# SHiB64_Mk_1Mod_2.net
KiCad netlist of a schematic drawn in EAGLE
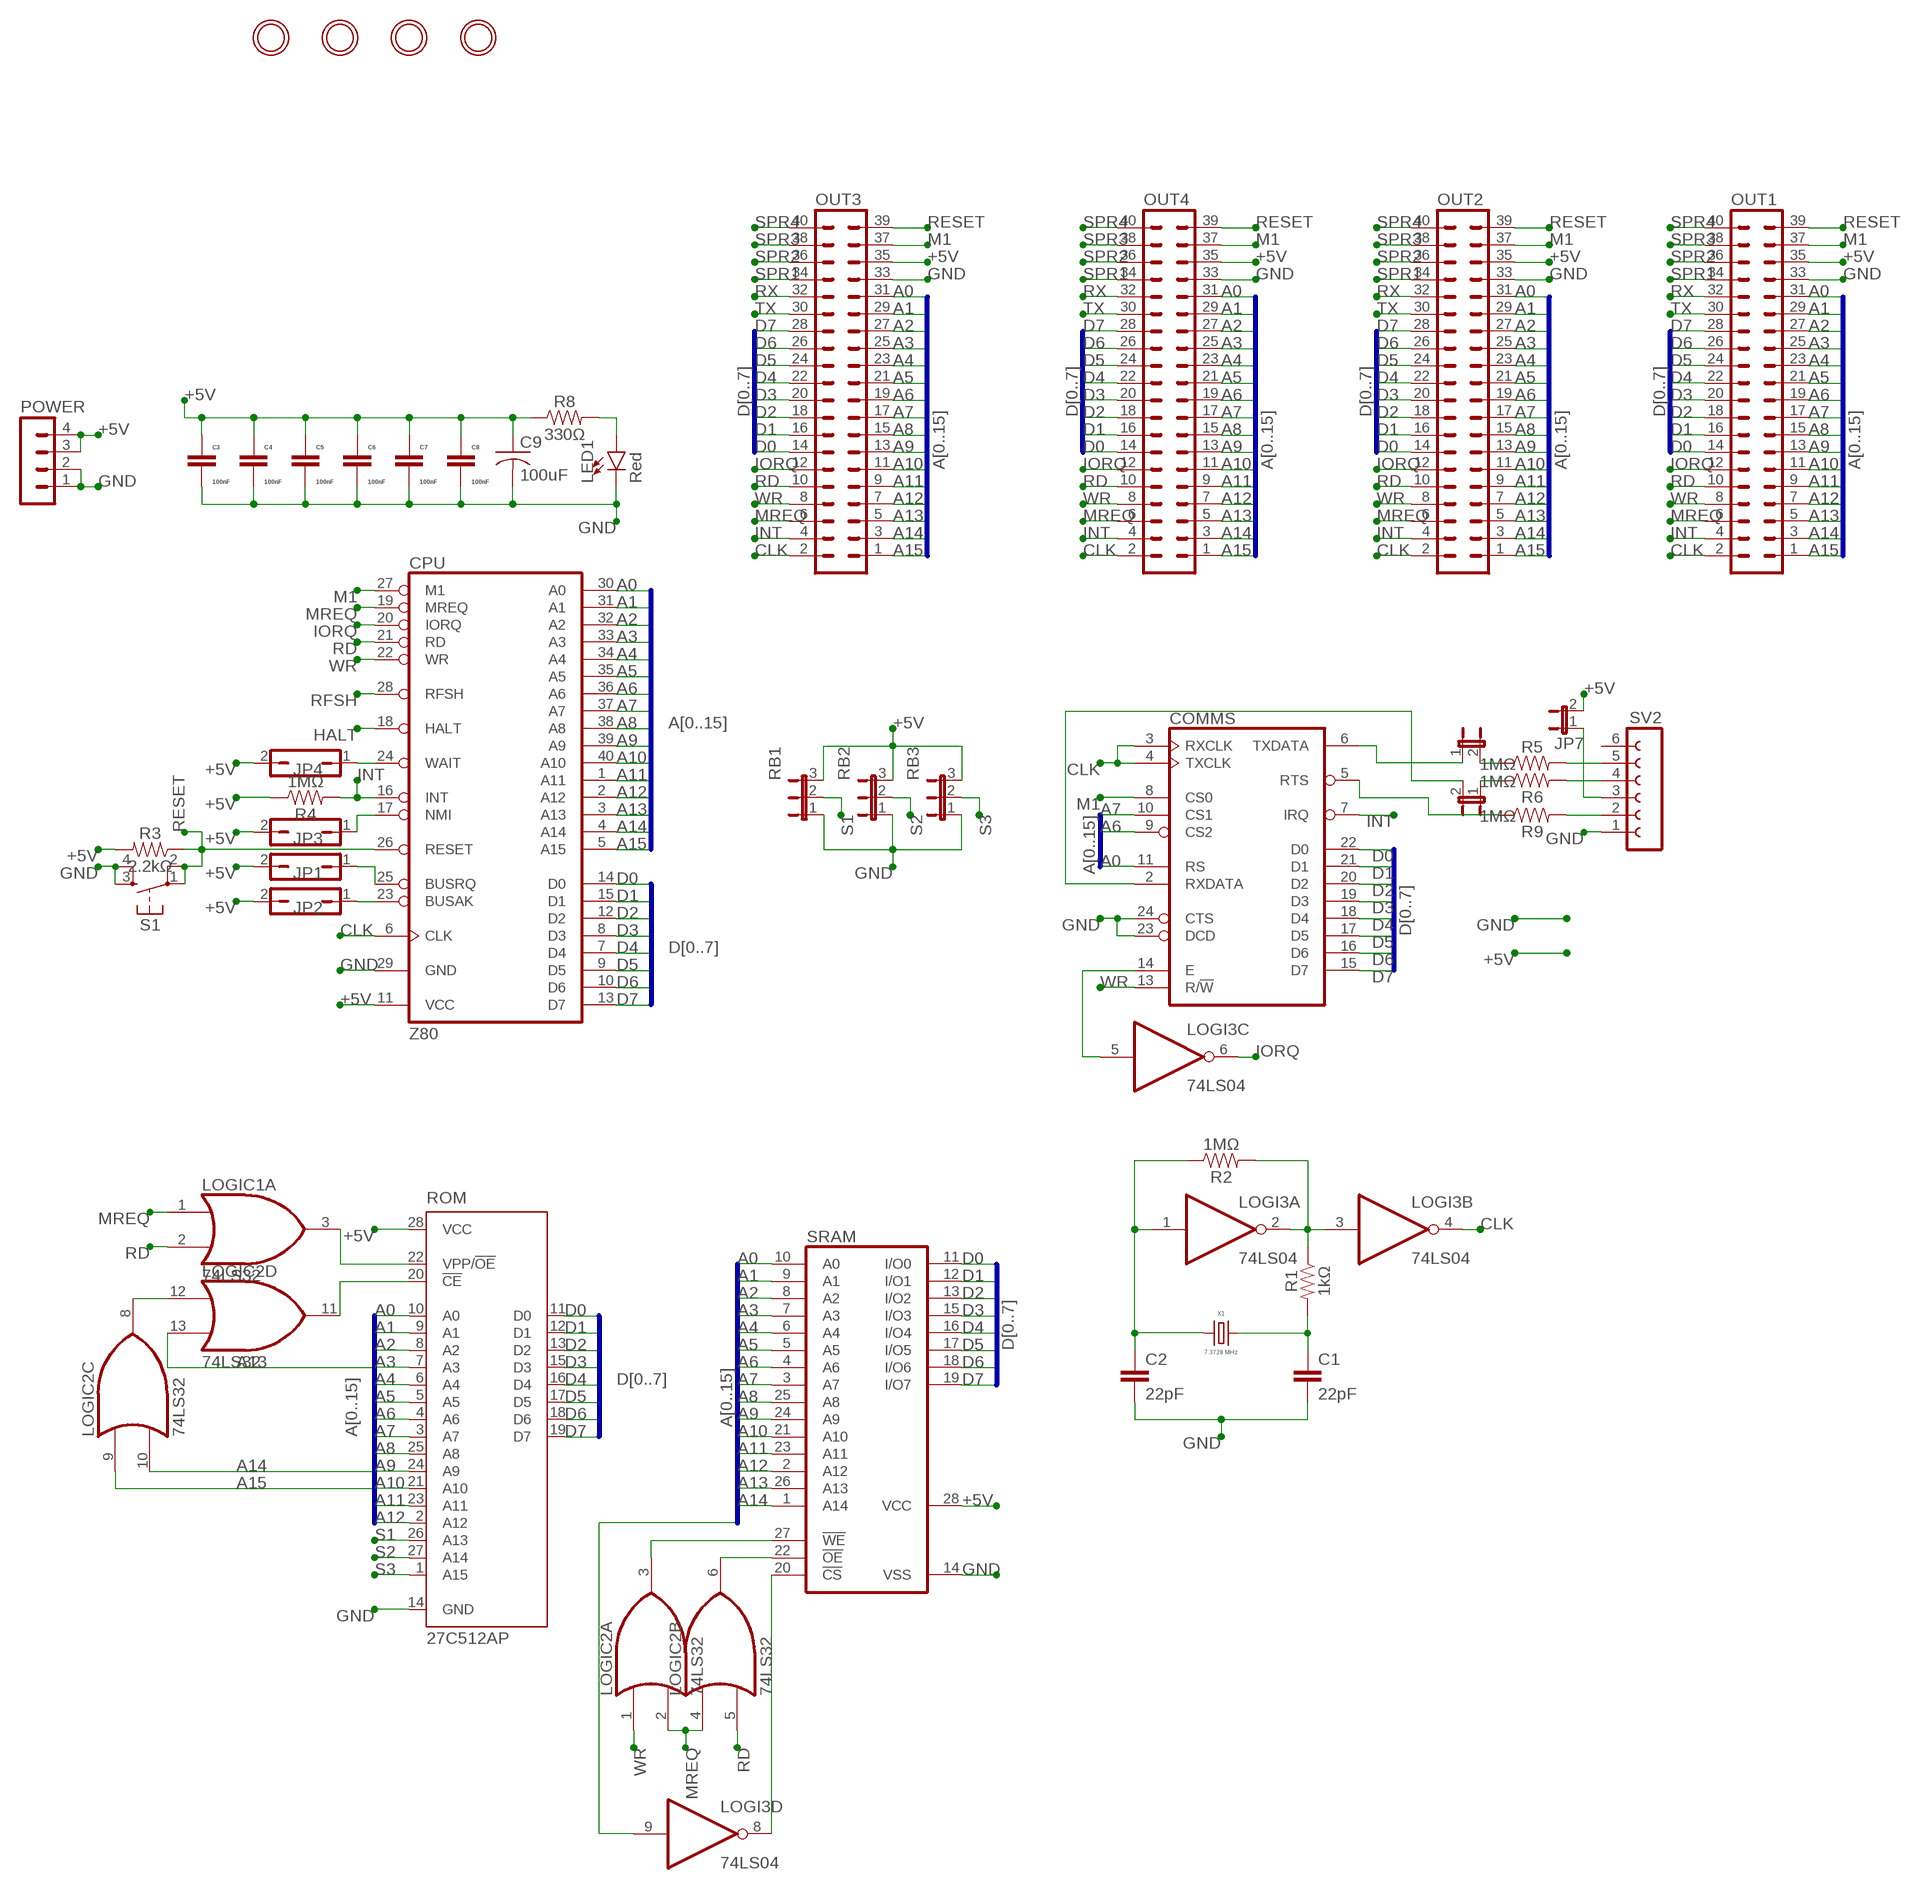
[diagram p0: schematic, sheet 1]

(export (version "E")
  (design (tool "Eeschema 10.0.6"))
  (components
    (comp (ref "C1")
      (value "22pF")
      (footprint "eagle-import:CAP-PTH-2.54")
      (libsource (lib "eagle-import") (part "CAP_DISK"))
    )
    (comp (ref "C2")
      (value "22pF")
      (footprint "eagle-import:CAP-PTH-2.54")
      (libsource (lib "eagle-import") (part "CAP_DISK"))
    )
    (comp (ref "C3")
      (value "100nF")
      (footprint "eagle-import:C1206")
      (libsource (lib "eagle-import") (part "CAPACITOR_1206_NONPPOLAR"))
    )
    (comp (ref "C4")
      (value "100nF")
      (footprint "eagle-import:C1206")
      (libsource (lib "eagle-import") (part "CAPACITOR_1206_NONPPOLAR"))
    )
    (comp (ref "C5")
      (value "100nF")
      (footprint "eagle-import:C1206")
      (libsource (lib "eagle-import") (part "CAPACITOR_1206_NONPPOLAR"))
    )
    (comp (ref "C6")
      (value "100nF")
      (footprint "eagle-import:C1206")
      (libsource (lib "eagle-import") (part "CAPACITOR_1206_NONPPOLAR"))
    )
    (comp (ref "C7")
      (value "100nF")
      (footprint "eagle-import:C1206")
      (libsource (lib "eagle-import") (part "CAPACITOR_1206_NONPPOLAR"))
    )
    (comp (ref "C8")
      (value "100nF")
      (footprint "eagle-import:C1206")
      (libsource (lib "eagle-import") (part "CAPACITOR_1206_NONPPOLAR"))
    )
    (comp (ref "C9")
      (value "100uF")
      (footprint "eagle-import:C1206")
      (libsource (lib "eagle-import") (part "CAPACITOR_1206_POLAR"))
    )
    (comp (ref "COMMS")
      (value "6850")
      (footprint "eagle-import:DIL24")
      (fields (field (name "MF") "NTE ELECTRONICS") (field (name "MPN") "NTE6850"))
      (libsource (lib "eagle-import") (part "6850"))
    )
    (comp (ref "CPU")
      (value "Z80")
      (footprint "eagle-import:DIL40")
      (libsource (lib "eagle-import") (part "Z80CPU"))
    )
    (comp (ref "JP1")
      (value "JP1Q")
      (footprint "eagle-import:JP1")
      (libsource (lib "eagle-import") (part "JP1Q"))
    )
    (comp (ref "JP2")
      (value "JP1Q")
      (footprint "eagle-import:JP1")
      (libsource (lib "eagle-import") (part "JP1Q"))
    )
    (comp (ref "JP3")
      (value "JP1Q")
      (footprint "eagle-import:JP1")
      (libsource (lib "eagle-import") (part "JP1Q"))
    )
    (comp (ref "JP4")
      (value "JP1Q")
      (footprint "eagle-import:JP1")
      (libsource (lib "eagle-import") (part "JP1Q"))
    )
    (comp (ref "JP5")
      (value "JP1E")
      (footprint "eagle-import:JP1")
      (libsource (lib "eagle-import") (part "JP1E"))
    )
    (comp (ref "JP6")
      (value "JP1E")
      (footprint "eagle-import:JP1")
      (libsource (lib "eagle-import") (part "JP1E"))
    )
    (comp (ref "JP7")
      (value "JP1E")
      (footprint "eagle-import:JP1")
      (libsource (lib "eagle-import") (part "JP1E"))
    )
    (comp (ref "LED1")
      (value "Red")
      (footprint "eagle-import:LED_1206")
      (libsource (lib "eagle-import") (part "LED_1206"))
    )
    (comp (ref "LOGI3")
      (value "74LS04")
      (footprint "eagle-import:SO14")
      (libsource (lib "eagle-import") (part "7404DALS"))
    )
    (comp (ref "LOGIC1")
      (value "74LS32")
      (footprint "eagle-import:SO14")
      (libsource (lib "eagle-import") (part "7432DLS"))
    )
    (comp (ref "LOGIC2")
      (value "74LS32")
      (footprint "eagle-import:SO14")
      (libsource (lib "eagle-import") (part "7432DLS"))
    )
    (comp (ref "OUT1")
      (value "MA20-2")
      (footprint "eagle-import:MA20-2")
      (libsource (lib "eagle-import") (part "MA20-2"))
    )
    (comp (ref "OUT2")
      (value "MA20-2")
      (footprint "eagle-import:MA20-2")
      (libsource (lib "eagle-import") (part "MA20-2"))
    )
    (comp (ref "OUT3")
      (value "MA20-2")
      (footprint "eagle-import:MA20-2")
      (libsource (lib "eagle-import") (part "MA20-2"))
    )
    (comp (ref "OUT4")
      (value "MA20-2")
      (footprint "eagle-import:MA20-2")
      (libsource (lib "eagle-import") (part "MA20-2"))
    )
    (comp (ref "POWER")
      (value "MA04-1")
      (footprint "eagle-import:MA04-1")
      (libsource (lib "eagle-import") (part "MA04-1"))
    )
    (comp (ref "R1")
      (value "1kΩ")
      (footprint "eagle-import:R1206")
      (libsource (lib "eagle-import") (part "RESISTOR"))
    )
    (comp (ref "R2")
      (value "1MΩ")
      (footprint "eagle-import:R1206")
      (libsource (lib "eagle-import") (part "RESISTOR"))
    )
    (comp (ref "R3")
      (value "2.2kΩ")
      (footprint "eagle-import:R1206")
      (libsource (lib "eagle-import") (part "RESISTOR"))
    )
    (comp (ref "R4")
      (value "1MΩ")
      (footprint "eagle-import:R1206")
      (libsource (lib "eagle-import") (part "RESISTOR"))
    )
    (comp (ref "R5")
      (value "1MΩ")
      (footprint "eagle-import:R1206")
      (libsource (lib "eagle-import") (part "RESISTOR"))
    )
    (comp (ref "R6")
      (value "1MΩ")
      (footprint "eagle-import:R1206")
      (libsource (lib "eagle-import") (part "RESISTOR"))
    )
    (comp (ref "R8")
      (value "330Ω")
      (footprint "eagle-import:R1206")
      (libsource (lib "eagle-import") (part "RESISTOR"))
    )
    (comp (ref "R9")
      (value "1MΩ")
      (footprint "eagle-import:R1206")
      (libsource (lib "eagle-import") (part "RESISTOR"))
    )
    (comp (ref "RB1")
      (value "JP2E")
      (footprint "eagle-import:JP2")
      (libsource (lib "eagle-import") (part "JP2E"))
    )
    (comp (ref "RB2")
      (value "JP2E")
      (footprint "eagle-import:JP2")
      (libsource (lib "eagle-import") (part "JP2E"))
    )
    (comp (ref "RB3")
      (value "JP2E")
      (footprint "eagle-import:JP2")
      (libsource (lib "eagle-import") (part "JP2E"))
    )
    (comp (ref "ROM")
      (value "27C512AP")
      (footprint "eagle-import:DIL28-6")
      (fields (field (name "MPN") "M27C512-90B6"))
      (libsource (lib "eagle-import") (part "27512APC"))
    )
    (comp (ref "S1")
      (value "MOMENTARY_BUTTONS6MMSMALL")
      (footprint "eagle-import:TACTILE_SWITCH_PTH_6.0MM")
      (libsource (lib "eagle-import") (part "MOMENTARY_BUTTONS6MMSMALL"))
    )
    (comp (ref "SRAM")
      (value "62256P")
      (footprint "eagle-import:DIL28-6")
      (libsource (lib "eagle-import") (part "62256P"))
    )
    (comp (ref "SV2")
      (value "FE06-1")
      (footprint "eagle-import:FE06")
      (libsource (lib "eagle-import") (part "FE06-1"))
    )
    (comp (ref "U$1")
      (value "MOUNTING_HOLE")
      (footprint "eagle-import:MOUNTINGHOLE_3.2MM_PLATEDTHIN")
      (libsource (lib "eagle-import") (part "MOUNTING_HOLE"))
    )
    (comp (ref "U$2")
      (value "MOUNTING_HOLE")
      (footprint "eagle-import:MOUNTINGHOLE_3.2MM_PLATEDTHIN")
      (libsource (lib "eagle-import") (part "MOUNTING_HOLE"))
    )
    (comp (ref "U$3")
      (value "MOUNTING_HOLE")
      (footprint "eagle-import:MOUNTINGHOLE_3.2MM_PLATEDTHIN")
      (libsource (lib "eagle-import") (part "MOUNTING_HOLE"))
    )
    (comp (ref "U$4")
      (value "MOUNTING_HOLE")
      (footprint "eagle-import:MOUNTINGHOLE_3.2MM_PLATEDTHIN")
      (libsource (lib "eagle-import") (part "MOUNTING_HOLE"))
    )
    (comp (ref "X1")
      (value "7.3728 MHz")
      (footprint "eagle-import:HC49US")
      (libsource (lib "eagle-import") (part "CRYSTAL_16MHZ"))
    )
  )
  (nets
    (net (code "1") (name "/+5V") (class "Default")
      (node (ref "C3") (pin "1") (pinfunction "1_1") (pintype "passive"))
      (node (ref "C4") (pin "1") (pinfunction "1_1") (pintype "passive"))
      (node (ref "C5") (pin "1") (pinfunction "1_1") (pintype "passive"))
      (node (ref "C6") (pin "1") (pinfunction "1_1") (pintype "passive"))
      (node (ref "C7") (pin "1") (pinfunction "1_1") (pintype "passive"))
      (node (ref "C8") (pin "1") (pinfunction "1_1") (pintype "passive"))
      (node (ref "C9") (pin "1") (pinfunction "1_1") (pintype "passive"))
      (node (ref "CPU") (pin "11") (pinfunction "VCC_11") (pintype "power_in"))
      (node (ref "JP1") (pin "2") (pinfunction "2_2") (pintype "passive"))
      (node (ref "JP2") (pin "2") (pinfunction "2_2") (pintype "passive"))
      (node (ref "JP3") (pin "2") (pinfunction "2_2") (pintype "passive"))
      (node (ref "JP4") (pin "2") (pinfunction "2_2") (pintype "passive"))
      (node (ref "JP7") (pin "2") (pinfunction "2_2") (pintype "passive"))
      (node (ref "OUT1") (pin "35") (pinfunction "35_35") (pintype "passive"))
      (node (ref "OUT2") (pin "35") (pinfunction "35_35") (pintype "passive"))
      (node (ref "OUT3") (pin "35") (pinfunction "35_35") (pintype "passive"))
      (node (ref "OUT4") (pin "35") (pinfunction "35_35") (pintype "passive"))
      (node (ref "POWER") (pin "3") (pinfunction "3_3") (pintype "passive"))
      (node (ref "POWER") (pin "4") (pinfunction "4_4") (pintype "passive"))
      (node (ref "R3") (pin "2") (pinfunction "2_2") (pintype "passive"))
      (node (ref "R4") (pin "1") (pinfunction "1_1") (pintype "passive"))
      (node (ref "R8") (pin "1") (pinfunction "1_1") (pintype "passive"))
      (node (ref "RB1") (pin "3") (pinfunction "3_3") (pintype "passive"))
      (node (ref "RB2") (pin "3") (pinfunction "3_3") (pintype "passive"))
      (node (ref "RB3") (pin "3") (pinfunction "3_3") (pintype "passive"))
      (node (ref "ROM") (pin "28") (pinfunction "VCC_28") (pintype "power_in"))
      (node (ref "SRAM") (pin "28") (pinfunction "VCC_28") (pintype "power_in"))
    )
    (net (code "2") (name "/A0") (class "Default")
      (node (ref "COMMS") (pin "11") (pinfunction "RS_11") (pintype "input"))
      (node (ref "CPU") (pin "30") (pinfunction "A0_30") (pintype "output"))
      (node (ref "OUT1") (pin "31") (pinfunction "31_31") (pintype "passive"))
      (node (ref "OUT2") (pin "31") (pinfunction "31_31") (pintype "passive"))
      (node (ref "OUT3") (pin "31") (pinfunction "31_31") (pintype "passive"))
      (node (ref "OUT4") (pin "31") (pinfunction "31_31") (pintype "passive"))
      (node (ref "ROM") (pin "10") (pinfunction "A0_10") (pintype "input"))
      (node (ref "SRAM") (pin "10") (pinfunction "A0_10") (pintype "input"))
    )
    (net (code "3") (name "/A1") (class "Default")
      (node (ref "CPU") (pin "31") (pinfunction "A1_31") (pintype "output"))
      (node (ref "OUT1") (pin "29") (pinfunction "29_29") (pintype "passive"))
      (node (ref "OUT2") (pin "29") (pinfunction "29_29") (pintype "passive"))
      (node (ref "OUT3") (pin "29") (pinfunction "29_29") (pintype "passive"))
      (node (ref "OUT4") (pin "29") (pinfunction "29_29") (pintype "passive"))
      (node (ref "ROM") (pin "9") (pinfunction "A1_9") (pintype "input"))
      (node (ref "SRAM") (pin "9") (pinfunction "A1_9") (pintype "input"))
    )
    (net (code "4") (name "/A2") (class "Default")
      (node (ref "CPU") (pin "32") (pinfunction "A2_32") (pintype "output"))
      (node (ref "OUT1") (pin "27") (pinfunction "27_27") (pintype "passive"))
      (node (ref "OUT2") (pin "27") (pinfunction "27_27") (pintype "passive"))
      (node (ref "OUT3") (pin "27") (pinfunction "27_27") (pintype "passive"))
      (node (ref "OUT4") (pin "27") (pinfunction "27_27") (pintype "passive"))
      (node (ref "ROM") (pin "8") (pinfunction "A2_8") (pintype "input"))
      (node (ref "SRAM") (pin "8") (pinfunction "A2_8") (pintype "input"))
    )
    (net (code "5") (name "/A3") (class "Default")
      (node (ref "CPU") (pin "33") (pinfunction "A3_33") (pintype "output"))
      (node (ref "OUT1") (pin "25") (pinfunction "25_25") (pintype "passive"))
      (node (ref "OUT2") (pin "25") (pinfunction "25_25") (pintype "passive"))
      (node (ref "OUT3") (pin "25") (pinfunction "25_25") (pintype "passive"))
      (node (ref "OUT4") (pin "25") (pinfunction "25_25") (pintype "passive"))
      (node (ref "ROM") (pin "7") (pinfunction "A3_7") (pintype "input"))
      (node (ref "SRAM") (pin "7") (pinfunction "A3_7") (pintype "input"))
    )
    (net (code "6") (name "/A4") (class "Default")
      (node (ref "CPU") (pin "34") (pinfunction "A4_34") (pintype "output"))
      (node (ref "OUT1") (pin "23") (pinfunction "23_23") (pintype "passive"))
      (node (ref "OUT2") (pin "23") (pinfunction "23_23") (pintype "passive"))
      (node (ref "OUT3") (pin "23") (pinfunction "23_23") (pintype "passive"))
      (node (ref "OUT4") (pin "23") (pinfunction "23_23") (pintype "passive"))
      (node (ref "ROM") (pin "6") (pinfunction "A4_6") (pintype "input"))
      (node (ref "SRAM") (pin "6") (pinfunction "A4_6") (pintype "input"))
    )
    (net (code "7") (name "/A5") (class "Default")
      (node (ref "CPU") (pin "35") (pinfunction "A5_35") (pintype "output"))
      (node (ref "OUT1") (pin "21") (pinfunction "21_21") (pintype "passive"))
      (node (ref "OUT2") (pin "21") (pinfunction "21_21") (pintype "passive"))
      (node (ref "OUT3") (pin "21") (pinfunction "21_21") (pintype "passive"))
      (node (ref "OUT4") (pin "21") (pinfunction "21_21") (pintype "passive"))
      (node (ref "ROM") (pin "5") (pinfunction "A5_5") (pintype "input"))
      (node (ref "SRAM") (pin "5") (pinfunction "A5_5") (pintype "input"))
    )
    (net (code "8") (name "/A6") (class "Default")
      (node (ref "COMMS") (pin "9") (pinfunction "CS2_9") (pintype "input"))
      (node (ref "CPU") (pin "36") (pinfunction "A6_36") (pintype "output"))
      (node (ref "OUT1") (pin "19") (pinfunction "19_19") (pintype "passive"))
      (node (ref "OUT2") (pin "19") (pinfunction "19_19") (pintype "passive"))
      (node (ref "OUT3") (pin "19") (pinfunction "19_19") (pintype "passive"))
      (node (ref "OUT4") (pin "19") (pinfunction "19_19") (pintype "passive"))
      (node (ref "ROM") (pin "4") (pinfunction "A6_4") (pintype "input"))
      (node (ref "SRAM") (pin "4") (pinfunction "A6_4") (pintype "input"))
    )
    (net (code "9") (name "/A7") (class "Default")
      (node (ref "COMMS") (pin "10") (pinfunction "CS1_10") (pintype "input"))
      (node (ref "CPU") (pin "37") (pinfunction "A7_37") (pintype "output"))
      (node (ref "OUT1") (pin "17") (pinfunction "17_17") (pintype "passive"))
      (node (ref "OUT2") (pin "17") (pinfunction "17_17") (pintype "passive"))
      (node (ref "OUT3") (pin "17") (pinfunction "17_17") (pintype "passive"))
      (node (ref "OUT4") (pin "17") (pinfunction "17_17") (pintype "passive"))
      (node (ref "ROM") (pin "3") (pinfunction "A7_3") (pintype "input"))
      (node (ref "SRAM") (pin "3") (pinfunction "A7_3") (pintype "input"))
    )
    (net (code "10") (name "/A8") (class "Default")
      (node (ref "CPU") (pin "38") (pinfunction "A8_38") (pintype "output"))
      (node (ref "OUT1") (pin "15") (pinfunction "15_15") (pintype "passive"))
      (node (ref "OUT2") (pin "15") (pinfunction "15_15") (pintype "passive"))
      (node (ref "OUT3") (pin "15") (pinfunction "15_15") (pintype "passive"))
      (node (ref "OUT4") (pin "15") (pinfunction "15_15") (pintype "passive"))
      (node (ref "ROM") (pin "25") (pinfunction "A8_25") (pintype "input"))
      (node (ref "SRAM") (pin "25") (pinfunction "A8_25") (pintype "input"))
    )
    (net (code "11") (name "/A9") (class "Default")
      (node (ref "CPU") (pin "39") (pinfunction "A9_39") (pintype "output"))
      (node (ref "OUT1") (pin "13") (pinfunction "13_13") (pintype "passive"))
      (node (ref "OUT2") (pin "13") (pinfunction "13_13") (pintype "passive"))
      (node (ref "OUT3") (pin "13") (pinfunction "13_13") (pintype "passive"))
      (node (ref "OUT4") (pin "13") (pinfunction "13_13") (pintype "passive"))
      (node (ref "ROM") (pin "24") (pinfunction "A9_24") (pintype "input"))
      (node (ref "SRAM") (pin "24") (pinfunction "A9_24") (pintype "input"))
    )
    (net (code "12") (name "/A10") (class "Default")
      (node (ref "CPU") (pin "40") (pinfunction "A10_40") (pintype "output"))
      (node (ref "OUT1") (pin "11") (pinfunction "11_11") (pintype "passive"))
      (node (ref "OUT2") (pin "11") (pinfunction "11_11") (pintype "passive"))
      (node (ref "OUT3") (pin "11") (pinfunction "11_11") (pintype "passive"))
      (node (ref "OUT4") (pin "11") (pinfunction "11_11") (pintype "passive"))
      (node (ref "ROM") (pin "21") (pinfunction "A10_21") (pintype "input"))
      (node (ref "SRAM") (pin "21") (pinfunction "A10_21") (pintype "input"))
    )
    (net (code "13") (name "/A11") (class "Default")
      (node (ref "CPU") (pin "1") (pinfunction "A11_1") (pintype "output"))
      (node (ref "OUT1") (pin "9") (pinfunction "9_9") (pintype "passive"))
      (node (ref "OUT2") (pin "9") (pinfunction "9_9") (pintype "passive"))
      (node (ref "OUT3") (pin "9") (pinfunction "9_9") (pintype "passive"))
      (node (ref "OUT4") (pin "9") (pinfunction "9_9") (pintype "passive"))
      (node (ref "ROM") (pin "23") (pinfunction "A11_23") (pintype "input"))
      (node (ref "SRAM") (pin "23") (pinfunction "A11_23") (pintype "input"))
    )
    (net (code "14") (name "/A12") (class "Default")
      (node (ref "CPU") (pin "2") (pinfunction "A12_2") (pintype "output"))
      (node (ref "OUT1") (pin "7") (pinfunction "7_7") (pintype "passive"))
      (node (ref "OUT2") (pin "7") (pinfunction "7_7") (pintype "passive"))
      (node (ref "OUT3") (pin "7") (pinfunction "7_7") (pintype "passive"))
      (node (ref "OUT4") (pin "7") (pinfunction "7_7") (pintype "passive"))
      (node (ref "ROM") (pin "2") (pinfunction "A12_2") (pintype "input"))
      (node (ref "SRAM") (pin "2") (pinfunction "A12_2") (pintype "input"))
    )
    (net (code "15") (name "/A13") (class "Default")
      (node (ref "CPU") (pin "3") (pinfunction "A13_3") (pintype "output"))
      (node (ref "LOGIC2") (pin "13") (pinfunction "I1_13") (pintype "input"))
      (node (ref "OUT1") (pin "5") (pinfunction "5_5") (pintype "passive"))
      (node (ref "OUT2") (pin "5") (pinfunction "5_5") (pintype "passive"))
      (node (ref "OUT3") (pin "5") (pinfunction "5_5") (pintype "passive"))
      (node (ref "OUT4") (pin "5") (pinfunction "5_5") (pintype "passive"))
      (node (ref "SRAM") (pin "26") (pinfunction "A13_26") (pintype "input"))
    )
    (net (code "16") (name "/A14") (class "Default")
      (node (ref "CPU") (pin "4") (pinfunction "A14_4") (pintype "output"))
      (node (ref "LOGIC2") (pin "10") (pinfunction "I1_10") (pintype "input"))
      (node (ref "OUT1") (pin "3") (pinfunction "3_3") (pintype "passive"))
      (node (ref "OUT2") (pin "3") (pinfunction "3_3") (pintype "passive"))
      (node (ref "OUT3") (pin "3") (pinfunction "3_3") (pintype "passive"))
      (node (ref "OUT4") (pin "3") (pinfunction "3_3") (pintype "passive"))
      (node (ref "SRAM") (pin "1") (pinfunction "A14_1") (pintype "input"))
    )
    (net (code "17") (name "/A15") (class "Default")
      (node (ref "CPU") (pin "5") (pinfunction "A15_5") (pintype "output"))
      (node (ref "LOGI3") (pin "9") (pinfunction "I_9") (pintype "input"))
      (node (ref "LOGIC2") (pin "9") (pinfunction "I0_9") (pintype "input"))
      (node (ref "OUT1") (pin "1") (pinfunction "1_1") (pintype "passive"))
      (node (ref "OUT2") (pin "1") (pinfunction "1_1") (pintype "passive"))
      (node (ref "OUT3") (pin "1") (pinfunction "1_1") (pintype "passive"))
      (node (ref "OUT4") (pin "1") (pinfunction "1_1") (pintype "passive"))
    )
    (net (code "19") (name "/CLK") (class "Default")
      (node (ref "COMMS") (pin "3") (pinfunction "RXCLK_3") (pintype "input"))
      (node (ref "COMMS") (pin "4") (pinfunction "TXCLK_4") (pintype "input"))
      (node (ref "CPU") (pin "6") (pinfunction "CLK_6") (pintype "input"))
      (node (ref "LOGI3") (pin "4") (pinfunction "O_4") (pintype "output"))
      (node (ref "OUT1") (pin "2") (pinfunction "2_2") (pintype "passive"))
      (node (ref "OUT2") (pin "2") (pinfunction "2_2") (pintype "passive"))
      (node (ref "OUT3") (pin "2") (pinfunction "2_2") (pintype "passive"))
      (node (ref "OUT4") (pin "2") (pinfunction "2_2") (pintype "passive"))
    )
    (net (code "20") (name "/D0") (class "Default")
      (node (ref "COMMS") (pin "22") (pinfunction "D0_22") (pintype "bidirectional"))
      (node (ref "CPU") (pin "14") (pinfunction "D0_14") (pintype "bidirectional"))
      (node (ref "OUT1") (pin "14") (pinfunction "14_14") (pintype "passive"))
      (node (ref "OUT2") (pin "14") (pinfunction "14_14") (pintype "passive"))
      (node (ref "OUT3") (pin "14") (pinfunction "14_14") (pintype "passive"))
      (node (ref "OUT4") (pin "14") (pinfunction "14_14") (pintype "passive"))
      (node (ref "ROM") (pin "11") (pinfunction "D0_11") (pintype "tri_state"))
      (node (ref "SRAM") (pin "11") (pinfunction "I/O0_11") (pintype "bidirectional"))
    )
    (net (code "21") (name "/D1") (class "Default")
      (node (ref "COMMS") (pin "21") (pinfunction "D1_21") (pintype "bidirectional"))
      (node (ref "CPU") (pin "15") (pinfunction "D1_15") (pintype "bidirectional"))
      (node (ref "OUT1") (pin "16") (pinfunction "16_16") (pintype "passive"))
      (node (ref "OUT2") (pin "16") (pinfunction "16_16") (pintype "passive"))
      (node (ref "OUT3") (pin "16") (pinfunction "16_16") (pintype "passive"))
      (node (ref "OUT4") (pin "16") (pinfunction "16_16") (pintype "passive"))
      (node (ref "ROM") (pin "12") (pinfunction "D1_12") (pintype "tri_state"))
      (node (ref "SRAM") (pin "12") (pinfunction "I/O1_12") (pintype "bidirectional"))
    )
    (net (code "22") (name "/D2") (class "Default")
      (node (ref "COMMS") (pin "20") (pinfunction "D2_20") (pintype "bidirectional"))
      (node (ref "CPU") (pin "12") (pinfunction "D2_12") (pintype "bidirectional"))
      (node (ref "OUT1") (pin "18") (pinfunction "18_18") (pintype "passive"))
      (node (ref "OUT2") (pin "18") (pinfunction "18_18") (pintype "passive"))
      (node (ref "OUT3") (pin "18") (pinfunction "18_18") (pintype "passive"))
      (node (ref "OUT4") (pin "18") (pinfunction "18_18") (pintype "passive"))
      (node (ref "ROM") (pin "13") (pinfunction "D2_13") (pintype "tri_state"))
      (node (ref "SRAM") (pin "13") (pinfunction "I/O2_13") (pintype "bidirectional"))
    )
    (net (code "23") (name "/D3") (class "Default")
      (node (ref "COMMS") (pin "19") (pinfunction "D3_19") (pintype "bidirectional"))
      (node (ref "CPU") (pin "8") (pinfunction "D3_8") (pintype "bidirectional"))
      (node (ref "OUT1") (pin "20") (pinfunction "20_20") (pintype "passive"))
      (node (ref "OUT2") (pin "20") (pinfunction "20_20") (pintype "passive"))
      (node (ref "OUT3") (pin "20") (pinfunction "20_20") (pintype "passive"))
      (node (ref "OUT4") (pin "20") (pinfunction "20_20") (pintype "passive"))
      (node (ref "ROM") (pin "15") (pinfunction "D3_15") (pintype "tri_state"))
      (node (ref "SRAM") (pin "15") (pinfunction "I/O3_15") (pintype "bidirectional"))
    )
    (net (code "24") (name "/D4") (class "Default")
      (node (ref "COMMS") (pin "18") (pinfunction "D4_18") (pintype "bidirectional"))
      (node (ref "CPU") (pin "7") (pinfunction "D4_7") (pintype "bidirectional"))
      (node (ref "OUT1") (pin "22") (pinfunction "22_22") (pintype "passive"))
      (node (ref "OUT2") (pin "22") (pinfunction "22_22") (pintype "passive"))
      (node (ref "OUT3") (pin "22") (pinfunction "22_22") (pintype "passive"))
      (node (ref "OUT4") (pin "22") (pinfunction "22_22") (pintype "passive"))
      (node (ref "ROM") (pin "16") (pinfunction "D4_16") (pintype "tri_state"))
      (node (ref "SRAM") (pin "16") (pinfunction "I/O4_16") (pintype "bidirectional"))
    )
    (net (code "25") (name "/D5") (class "Default")
      (node (ref "COMMS") (pin "17") (pinfunction "D5_17") (pintype "bidirectional"))
      (node (ref "CPU") (pin "9") (pinfunction "D5_9") (pintype "bidirectional"))
      (node (ref "OUT1") (pin "24") (pinfunction "24_24") (pintype "passive"))
      (node (ref "OUT2") (pin "24") (pinfunction "24_24") (pintype "passive"))
      (node (ref "OUT3") (pin "24") (pinfunction "24_24") (pintype "passive"))
      (node (ref "OUT4") (pin "24") (pinfunction "24_24") (pintype "passive"))
      (node (ref "ROM") (pin "17") (pinfunction "D5_17") (pintype "tri_state"))
      (node (ref "SRAM") (pin "17") (pinfunction "I/O5_17") (pintype "bidirectional"))
    )
    (net (code "26") (name "/D6") (class "Default")
      (node (ref "COMMS") (pin "16") (pinfunction "D6_16") (pintype "bidirectional"))
      (node (ref "CPU") (pin "10") (pinfunction "D6_10") (pintype "bidirectional"))
      (node (ref "OUT1") (pin "26") (pinfunction "26_26") (pintype "passive"))
      (node (ref "OUT2") (pin "26") (pinfunction "26_26") (pintype "passive"))
      (node (ref "OUT3") (pin "26") (pinfunction "26_26") (pintype "passive"))
      (node (ref "OUT4") (pin "26") (pinfunction "26_26") (pintype "passive"))
      (node (ref "ROM") (pin "18") (pinfunction "D6_18") (pintype "tri_state"))
      (node (ref "SRAM") (pin "18") (pinfunction "I/O6_18") (pintype "bidirectional"))
    )
    (net (code "27") (name "/D7") (class "Default")
      (node (ref "COMMS") (pin "15") (pinfunction "D7_15") (pintype "bidirectional"))
      (node (ref "CPU") (pin "13") (pinfunction "D7_13") (pintype "bidirectional"))
      (node (ref "OUT1") (pin "28") (pinfunction "28_28") (pintype "passive"))
      (node (ref "OUT2") (pin "28") (pinfunction "28_28") (pintype "passive"))
      (node (ref "OUT3") (pin "28") (pinfunction "28_28") (pintype "passive"))
      (node (ref "OUT4") (pin "28") (pinfunction "28_28") (pintype "passive"))
      (node (ref "ROM") (pin "19") (pinfunction "D7_19") (pintype "tri_state"))
      (node (ref "SRAM") (pin "19") (pinfunction "I/O7_19") (pintype "bidirectional"))
    )
    (net (code "29") (name "/GND") (class "Default")
      (node (ref "C1") (pin "2") (pinfunction "2_2") (pintype "passive"))
      (node (ref "C2") (pin "2") (pinfunction "2_2") (pintype "passive"))
      (node (ref "C3") (pin "2") (pinfunction "2_2") (pintype "passive"))
      (node (ref "C4") (pin "2") (pinfunction "2_2") (pintype "passive"))
      (node (ref "C5") (pin "2") (pinfunction "2_2") (pintype "passive"))
      (node (ref "C6") (pin "2") (pinfunction "2_2") (pintype "passive"))
      (node (ref "C7") (pin "2") (pinfunction "2_2") (pintype "passive"))
      (node (ref "C8") (pin "2") (pinfunction "2_2") (pintype "passive"))
      (node (ref "C9") (pin "2") (pinfunction "2_2") (pintype "passive"))
      (node (ref "COMMS") (pin "23") (pinfunction "DCD_23") (pintype "input"))
      (node (ref "COMMS") (pin "24") (pinfunction "CTS_24") (pintype "input"))
      (node (ref "CPU") (pin "29") (pinfunction "GND_29") (pintype "power_in"))
      (node (ref "LED1") (pin "-") (pinfunction "C_-") (pintype "passive"))
      (node (ref "OUT1") (pin "33") (pinfunction "33_33") (pintype "passive"))
      (node (ref "OUT2") (pin "33") (pinfunction "33_33") (pintype "passive"))
      (node (ref "OUT3") (pin "33") (pinfunction "33_33") (pintype "passive"))
      (node (ref "OUT4") (pin "33") (pinfunction "33_33") (pintype "passive"))
      (node (ref "POWER") (pin "1") (pinfunction "1_1") (pintype "passive"))
      (node (ref "POWER") (pin "2") (pinfunction "2_2") (pintype "passive"))
      (node (ref "RB1") (pin "1") (pinfunction "1_1") (pintype "passive"))
      (node (ref "RB2") (pin "1") (pinfunction "1_1") (pintype "passive"))
      (node (ref "RB3") (pin "1") (pinfunction "1_1") (pintype "passive"))
      (node (ref "ROM") (pin "14") (pinfunction "GND_14") (pintype "power_in"))
      (node (ref "S1") (pin "3") (pinfunction "S_3") (pintype "passive"))
      (node (ref "S1") (pin "4") (pinfunction "S1_4") (pintype "passive"))
      (node (ref "SRAM") (pin "14") (pinfunction "VSS_14") (pintype "power_in"))
      (node (ref "SV2") (pin "1") (pinfunction "1_1") (pintype "passive"))
    )
    (net (code "30") (name "/HALT") (class "Default")
      (node (ref "CPU") (pin "18") (pinfunction "HALT_18") (pintype "output"))
    )
    (net (code "31") (name "/INT") (class "Default")
      (node (ref "COMMS") (pin "7") (pinfunction "IRQ_7") (pintype "output"))
      (node (ref "CPU") (pin "16") (pinfunction "INT_16") (pintype "input"))
      (node (ref "OUT1") (pin "4") (pinfunction "4_4") (pintype "passive"))
      (node (ref "OUT2") (pin "4") (pinfunction "4_4") (pintype "passive"))
      (node (ref "OUT3") (pin "4") (pinfunction "4_4") (pintype "passive"))
      (node (ref "OUT4") (pin "4") (pinfunction "4_4") (pintype "passive"))
      (node (ref "R4") (pin "2") (pinfunction "2_2") (pintype "passive"))
    )
    (net (code "32") (name "/IORQ") (class "Default")
      (node (ref "CPU") (pin "20") (pinfunction "IORQ_20") (pintype "output"))
      (node (ref "LOGI3") (pin "6") (pinfunction "O_6") (pintype "output"))
      (node (ref "OUT1") (pin "12") (pinfunction "12_12") (pintype "passive"))
      (node (ref "OUT2") (pin "12") (pinfunction "12_12") (pintype "passive"))
      (node (ref "OUT3") (pin "12") (pinfunction "12_12") (pintype "passive"))
      (node (ref "OUT4") (pin "12") (pinfunction "12_12") (pintype "passive"))
    )
    (net (code "33") (name "/M1") (class "Default")
      (node (ref "COMMS") (pin "8") (pinfunction "CS0_8") (pintype "input"))
      (node (ref "CPU") (pin "27") (pinfunction "M1_27") (pintype "output"))
      (node (ref "OUT1") (pin "37") (pinfunction "37_37") (pintype "passive"))
      (node (ref "OUT2") (pin "37") (pinfunction "37_37") (pintype "passive"))
      (node (ref "OUT3") (pin "37") (pinfunction "37_37") (pintype "passive"))
      (node (ref "OUT4") (pin "37") (pinfunction "37_37") (pintype "passive"))
    )
    (net (code "34") (name "/MREQ") (class "Default")
      (node (ref "CPU") (pin "19") (pinfunction "MREQ_19") (pintype "output"))
      (node (ref "LOGIC1") (pin "1") (pinfunction "I0_1") (pintype "input"))
      (node (ref "LOGIC2") (pin "2") (pinfunction "I1_2") (pintype "input"))
      (node (ref "LOGIC2") (pin "4") (pinfunction "I0_4") (pintype "input"))
      (node (ref "OUT1") (pin "6") (pinfunction "6_6") (pintype "passive"))
      (node (ref "OUT2") (pin "6") (pinfunction "6_6") (pintype "passive"))
      (node (ref "OUT3") (pin "6") (pinfunction "6_6") (pintype "passive"))
      (node (ref "OUT4") (pin "6") (pinfunction "6_6") (pintype "passive"))
    )
    (net (code "35") (name "/RD") (class "Default")
      (node (ref "CPU") (pin "21") (pinfunction "RD_21") (pintype "output"))
      (node (ref "LOGIC1") (pin "2") (pinfunction "I1_2") (pintype "input"))
      (node (ref "LOGIC2") (pin "5") (pinfunction "I1_5") (pintype "input"))
      (node (ref "OUT1") (pin "10") (pinfunction "10_10") (pintype "passive"))
      (node (ref "OUT2") (pin "10") (pinfunction "10_10") (pintype "passive"))
      (node (ref "OUT3") (pin "10") (pinfunction "10_10") (pintype "passive"))
      (node (ref "OUT4") (pin "10") (pinfunction "10_10") (pintype "passive"))
    )
    (net (code "36") (name "/RESET") (class "Default")
      (node (ref "CPU") (pin "26") (pinfunction "RESET_26") (pintype "input"))
      (node (ref "OUT1") (pin "39") (pinfunction "39_39") (pintype "passive"))
      (node (ref "OUT2") (pin "39") (pinfunction "39_39") (pintype "passive"))
      (node (ref "OUT3") (pin "39") (pinfunction "39_39") (pintype "passive"))
      (node (ref "OUT4") (pin "39") (pinfunction "39_39") (pintype "passive"))
      (node (ref "R3") (pin "1") (pinfunction "1_1") (pintype "passive"))
      (node (ref "S1") (pin "1") (pinfunction "P_1") (pintype "passive"))
      (node (ref "S1") (pin "2") (pinfunction "P1_2") (pintype "passive"))
    )
    (net (code "37") (name "/RFSH") (class "Default")
      (node (ref "CPU") (pin "28") (pinfunction "RFSH_28") (pintype "output"))
    )
    (net (code "38") (name "/RX") (class "Default")
      (node (ref "OUT1") (pin "32") (pinfunction "32_32") (pintype "passive"))
      (node (ref "OUT2") (pin "32") (pinfunction "32_32") (pintype "passive"))
      (node (ref "OUT3") (pin "32") (pinfunction "32_32") (pintype "passive"))
      (node (ref "OUT4") (pin "32") (pinfunction "32_32") (pintype "passive"))
    )
    (net (code "39") (name "/S1") (class "Default")
      (node (ref "RB1") (pin "2") (pinfunction "2_2") (pintype "passive"))
      (node (ref "ROM") (pin "26") (pinfunction "A13_26") (pintype "input"))
    )
    (net (code "40") (name "/S2") (class "Default")
      (node (ref "RB2") (pin "2") (pinfunction "2_2") (pintype "passive"))
      (node (ref "ROM") (pin "27") (pinfunction "A14_27") (pintype "input"))
    )
    (net (code "41") (name "/S3") (class "Default")
      (node (ref "RB3") (pin "2") (pinfunction "2_2") (pintype "passive"))
      (node (ref "ROM") (pin "1") (pinfunction "A15_1") (pintype "input"))
    )
    (net (code "42") (name "/SPR1") (class "Default")
      (node (ref "OUT1") (pin "34") (pinfunction "34_34") (pintype "passive"))
      (node (ref "OUT2") (pin "34") (pinfunction "34_34") (pintype "passive"))
      (node (ref "OUT3") (pin "34") (pinfunction "34_34") (pintype "passive"))
      (node (ref "OUT4") (pin "34") (pinfunction "34_34") (pintype "passive"))
    )
    (net (code "43") (name "/SPR2") (class "Default")
      (node (ref "OUT1") (pin "36") (pinfunction "36_36") (pintype "passive"))
      (node (ref "OUT2") (pin "36") (pinfunction "36_36") (pintype "passive"))
      (node (ref "OUT3") (pin "36") (pinfunction "36_36") (pintype "passive"))
      (node (ref "OUT4") (pin "36") (pinfunction "36_36") (pintype "passive"))
    )
    (net (code "44") (name "/SPR3") (class "Default")
      (node (ref "OUT1") (pin "38") (pinfunction "38_38") (pintype "passive"))
      (node (ref "OUT2") (pin "38") (pinfunction "38_38") (pintype "passive"))
      (node (ref "OUT3") (pin "38") (pinfunction "38_38") (pintype "passive"))
      (node (ref "OUT4") (pin "38") (pinfunction "38_38") (pintype "passive"))
    )
    (net (code "45") (name "/SPR4") (class "Default")
      (node (ref "OUT1") (pin "40") (pinfunction "40_40") (pintype "passive"))
      (node (ref "OUT2") (pin "40") (pinfunction "40_40") (pintype "passive"))
      (node (ref "OUT3") (pin "40") (pinfunction "40_40") (pintype "passive"))
      (node (ref "OUT4") (pin "40") (pinfunction "40_40") (pintype "passive"))
    )
    (net (code "46") (name "/TX") (class "Default")
      (node (ref "OUT1") (pin "30") (pinfunction "30_30") (pintype "passive"))
      (node (ref "OUT2") (pin "30") (pinfunction "30_30") (pintype "passive"))
      (node (ref "OUT3") (pin "30") (pinfunction "30_30") (pintype "passive"))
      (node (ref "OUT4") (pin "30") (pinfunction "30_30") (pintype "passive"))
    )
    (net (code "47") (name "/WR") (class "Default")
      (node (ref "COMMS") (pin "13") (pinfunction "R/~{W}_13") (pintype "input"))
      (node (ref "CPU") (pin "22") (pinfunction "WR_22") (pintype "output"))
      (node (ref "LOGIC2") (pin "1") (pinfunction "I0_1") (pintype "input"))
      (node (ref "OUT1") (pin "8") (pinfunction "8_8") (pintype "passive"))
      (node (ref "OUT2") (pin "8") (pinfunction "8_8") (pintype "passive"))
      (node (ref "OUT3") (pin "8") (pinfunction "8_8") (pintype "passive"))
      (node (ref "OUT4") (pin "8") (pinfunction "8_8") (pintype "passive"))
    )
    (net (code "48") (name "Net-(C1-Pad1)") (class "Default")
      (node (ref "C1") (pin "1") (pinfunction "1_1") (pintype "passive"))
      (node (ref "R1") (pin "2") (pinfunction "2_2") (pintype "passive"))
      (node (ref "X1") (pin "2") (pinfunction "2_2") (pintype "passive"))
    )
    (net (code "49") (name "Net-(COMMSA-E)") (class "Default")
      (node (ref "COMMS") (pin "14") (pinfunction "E_14") (pintype "input"))
      (node (ref "LOGI3") (pin "5") (pinfunction "I_5") (pintype "input"))
    )
    (net (code "50") (name "Net-(COMMSA-RTS)") (class "Default")
      (node (ref "COMMS") (pin "5") (pinfunction "RTS_5") (pintype "output"))
      (node (ref "R9") (pin "1") (pinfunction "1_1") (pintype "passive"))
    )
    (net (code "51") (name "Net-(COMMSA-RXDATA)") (class "Default")
      (node (ref "COMMS") (pin "2") (pinfunction "RXDATA_2") (pintype "input"))
      (node (ref "JP6") (pin "2") (pinfunction "2_2") (pintype "passive"))
    )
    (net (code "52") (name "Net-(COMMSA-TXDATA)") (class "Default")
      (node (ref "COMMS") (pin "6") (pinfunction "TXDATA_6") (pintype "output"))
      (node (ref "JP5") (pin "1") (pinfunction "1_1") (pintype "passive"))
    )
    (net (code "53") (name "Net-(CPU-BUSAK)") (class "Default")
      (node (ref "CPU") (pin "23") (pinfunction "BUSAK_23") (pintype "output"))
      (node (ref "JP2") (pin "1") (pinfunction "1_1") (pintype "passive"))
    )
    (net (code "54") (name "Net-(CPU-BUSRQ)") (class "Default")
      (node (ref "CPU") (pin "25") (pinfunction "BUSRQ_25") (pintype "input"))
      (node (ref "JP1") (pin "1") (pinfunction "1_1") (pintype "passive"))
    )
    (net (code "55") (name "Net-(CPU-NMI)") (class "Default")
      (node (ref "CPU") (pin "17") (pinfunction "NMI_17") (pintype "input"))
      (node (ref "JP3") (pin "1") (pinfunction "1_1") (pintype "passive"))
    )
    (net (code "56") (name "Net-(CPU-WAIT)") (class "Default")
      (node (ref "CPU") (pin "24") (pinfunction "WAIT_24") (pintype "input"))
      (node (ref "JP4") (pin "1") (pinfunction "1_1") (pintype "passive"))
    )
    (net (code "57") (name "Net-(JP5-Pad2)") (class "Default")
      (node (ref "JP5") (pin "2") (pinfunction "2_2") (pintype "passive"))
      (node (ref "R5") (pin "1") (pinfunction "1_1") (pintype "passive"))
    )
    (net (code "58") (name "Net-(JP6-Pad1)") (class "Default")
      (node (ref "JP6") (pin "1") (pinfunction "1_1") (pintype "passive"))
      (node (ref "R6") (pin "1") (pinfunction "1_1") (pintype "passive"))
    )
    (net (code "59") (name "Net-(JP7-Pad1)") (class "Default")
      (node (ref "JP7") (pin "1") (pinfunction "1_1") (pintype "passive"))
      (node (ref "SV2") (pin "3") (pinfunction "3_3") (pintype "passive"))
    )
    (net (code "60") (name "Net-(LED1-A)") (class "Default")
      (node (ref "LED1") (pin "+") (pinfunction "A_+") (pintype "passive"))
      (node (ref "R8") (pin "2") (pinfunction "2_2") (pintype "passive"))
    )
    (net (code "61") (name "Net-(LOGI3A-I)") (class "Default")
      (node (ref "C2") (pin "1") (pinfunction "1_1") (pintype "passive"))
      (node (ref "LOGI3") (pin "1") (pinfunction "I_1") (pintype "input"))
      (node (ref "R2") (pin "1") (pinfunction "1_1") (pintype "passive"))
      (node (ref "X1") (pin "1") (pinfunction "1_1") (pintype "passive"))
    )
    (net (code "62") (name "Net-(LOGI3A-O)") (class "Default")
      (node (ref "LOGI3") (pin "2") (pinfunction "O_2") (pintype "output"))
      (node (ref "LOGI3") (pin "3") (pinfunction "I_3") (pintype "input"))
      (node (ref "R1") (pin "1") (pinfunction "1_1") (pintype "passive"))
      (node (ref "R2") (pin "2") (pinfunction "2_2") (pintype "passive"))
    )
    (net (code "63") (name "Net-(LOGI3D-O)") (class "Default")
      (node (ref "LOGI3") (pin "8") (pinfunction "O_8") (pintype "output"))
      (node (ref "SRAM") (pin "20") (pinfunction "~{CS}_20") (pintype "input"))
    )
    (net (code "64") (name "Net-(LOGIC1A-O)") (class "Default")
      (node (ref "LOGIC1") (pin "3") (pinfunction "O_3") (pintype "output"))
      (node (ref "ROM") (pin "22") (pinfunction "VPP/~{OE}_22") (pintype "input"))
    )
    (net (code "65") (name "Net-(LOGIC2A-O)") (class "Default")
      (node (ref "LOGIC2") (pin "3") (pinfunction "O_3") (pintype "output"))
      (node (ref "SRAM") (pin "27") (pinfunction "~{WE}_27") (pintype "input"))
    )
    (net (code "66") (name "Net-(LOGIC2B-O)") (class "Default")
      (node (ref "LOGIC2") (pin "6") (pinfunction "O_6") (pintype "output"))
      (node (ref "SRAM") (pin "22") (pinfunction "~{OE}_22") (pintype "input"))
    )
    (net (code "67") (name "Net-(LOGIC2C-O)") (class "Default")
      (node (ref "LOGIC2") (pin "12") (pinfunction "I0_12") (pintype "input"))
      (node (ref "LOGIC2") (pin "8") (pinfunction "O_8") (pintype "output"))
    )
    (net (code "68") (name "Net-(LOGIC2D-O)") (class "Default")
      (node (ref "LOGIC2") (pin "11") (pinfunction "O_11") (pintype "output"))
      (node (ref "ROM") (pin "20") (pinfunction "~{CE}_20") (pintype "input"))
    )
    (net (code "69") (name "Net-(R5-Pad2)") (class "Default")
      (node (ref "R5") (pin "2") (pinfunction "2_2") (pintype "passive"))
      (node (ref "SV2") (pin "5") (pinfunction "5_5") (pintype "passive"))
    )
    (net (code "70") (name "Net-(R6-Pad2)") (class "Default")
      (node (ref "R6") (pin "2") (pinfunction "2_2") (pintype "passive"))
      (node (ref "SV2") (pin "4") (pinfunction "4_4") (pintype "passive"))
    )
    (net (code "71") (name "Net-(R9-Pad2)") (class "Default")
      (node (ref "R9") (pin "2") (pinfunction "2_2") (pintype "passive"))
      (node (ref "SV2") (pin "2") (pinfunction "2_2") (pintype "passive"))
    )
    (net (code "72") (name "unconnected-(SV2-Pad6)") (class "Default")
      (node (ref "SV2") (pin "6") (pinfunction "6_6") (pintype "passive"))
    )
  )
)
